# design.net
KiCad netlist of a schematic drawn in Altium Designer
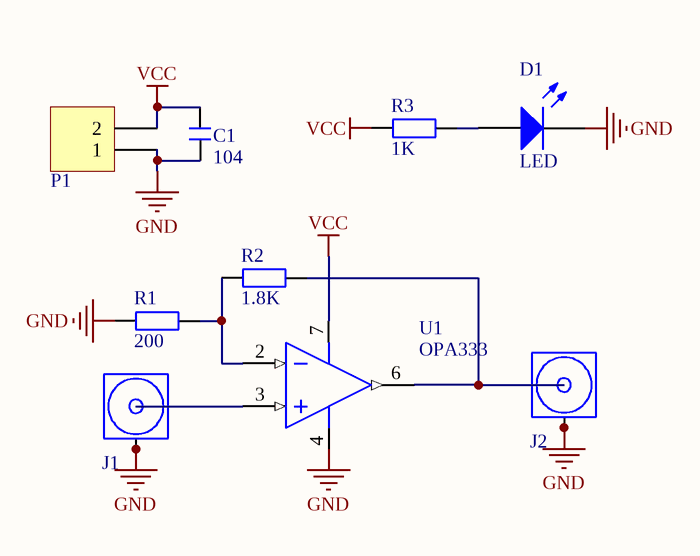
[diagram p0: 单电源同向放大器.SchDoc]

(export (version "E")
  (design (tool "Eeschema 10.0.6"))
  (components
    (comp (ref "C1")
      (value "104")
      (footprint "C 0805")
      (description "无极性贴片电容")
      (fields (field (name "版权归属") "源创客"))
      (libsource (lib "电阻-电容-电感") (part "C"))
    )
    (comp (ref "D1")
      (value "LED")
      (footprint "LED_0805")
      (description "发光二极管")
      (fields (field (name "PUBLISHER") "Altium Limited"))
      (libsource (lib "LIB") (part "LED"))
    )
    (comp (ref "J1") (value "COAX") (footprint "MCX5.08-5-H") (libsource (lib "LIB") (part "COAX")))
    (comp (ref "J2") (value "COAX") (footprint "MCX5.08-5-H") (libsource (lib "LIB") (part "COAX")))
    (comp (ref "P1")
      (value "Header 2")
      (footprint "HDR2X1_B2")
      (description "接插件")
      (fields (field (name "PUBLISHER") "Altium Limited"))
      (libsource (lib "LIB") (part "Header 2"))
    )
    (comp (ref "R1")
      (value "200")
      (footprint "R 0805")
      (description "贴片电阻")
      (fields (field (name "版权归属") "源创客"))
      (libsource (lib "电阻-电容-电感") (part "R"))
    )
    (comp (ref "R2")
      (value "1.8K")
      (footprint "R 0805")
      (description "贴片电阻")
      (fields (field (name "版权归属") "源创客"))
      (libsource (lib "电阻-电容-电感") (part "R"))
    )
    (comp (ref "R3")
      (value "1K")
      (footprint "R 0805")
      (description "贴片电阻")
      (fields (field (name "版权归属") "源创客"))
      (libsource (lib "电阻-电容-电感") (part "R"))
    )
    (comp (ref "U1")
      (value "OPA333")
      (footprint "SO8_L")
      (description "1.8V 微功耗 CMOS 运算放大器零漂移系列")
      (libsource (lib "LIB") (part "OPA333"))
    )
  )
  (nets
    (net (code "1") (name "GND") (class "Default")
      (node (ref "C1") (pin "1") (pinfunction "1_1") (pintype "passive"))
      (node (ref "D1") (pin "2") (pinfunction "K_2") (pintype "passive"))
      (node (ref "J1") (pin "2") (pinfunction "GND_2") (pintype "passive"))
      (node (ref "J1") (pin "3") (pinfunction "GND_3") (pintype "passive"))
      (node (ref "J1") (pin "4") (pinfunction "GND_4") (pintype "passive"))
      (node (ref "J1") (pin "5") (pinfunction "GND_5") (pintype "passive"))
      (node (ref "J2") (pin "2") (pinfunction "GND_2") (pintype "passive"))
      (node (ref "J2") (pin "3") (pinfunction "GND_3") (pintype "passive"))
      (node (ref "J2") (pin "4") (pinfunction "GND_4") (pintype "passive"))
      (node (ref "J2") (pin "5") (pinfunction "GND_5") (pintype "passive"))
      (node (ref "P1") (pin "1") (pinfunction "1_1") (pintype "passive"))
      (node (ref "R1") (pin "1") (pinfunction "1_1") (pintype "passive"))
      (node (ref "U1") (pin "4") (pinfunction "V-_4") (pintype "power_in"))
    )
    (net (code "2") (name "Net-(D1-A)") (class "Default")
      (node (ref "D1") (pin "1") (pinfunction "A_1") (pintype "passive"))
      (node (ref "R3") (pin "2") (pinfunction "2_2") (pintype "passive"))
    )
    (net (code "3") (name "Net-(J1-Signal)") (class "Default")
      (node (ref "J1") (pin "1") (pinfunction "Signal_1") (pintype "passive"))
      (node (ref "U1") (pin "3") (pinfunction "IN+_3") (pintype "input"))
    )
    (net (code "4") (name "Net-(J2-Signal)") (class "Default")
      (node (ref "J2") (pin "1") (pinfunction "Signal_1") (pintype "passive"))
      (node (ref "R2") (pin "2") (pinfunction "2_2") (pintype "passive"))
      (node (ref "U1") (pin "6") (pinfunction "OUT_6") (pintype "output"))
    )
    (net (code "5") (name "Net-(U1-IN-)") (class "Default")
      (node (ref "R1") (pin "2") (pinfunction "2_2") (pintype "passive"))
      (node (ref "R2") (pin "1") (pinfunction "1_1") (pintype "passive"))
      (node (ref "U1") (pin "2") (pinfunction "IN-_2") (pintype "input"))
    )
    (net (code "6") (name "VCC") (class "Default")
      (node (ref "C1") (pin "2") (pinfunction "2_2") (pintype "passive"))
      (node (ref "P1") (pin "2") (pinfunction "2_2") (pintype "passive"))
      (node (ref "R3") (pin "1") (pinfunction "1_1") (pintype "passive"))
      (node (ref "U1") (pin "7") (pinfunction "V+_7") (pintype "power_in"))
    )
  )
)
